# RS485.net
KiCad netlist of a schematic drawn in Altium Designer
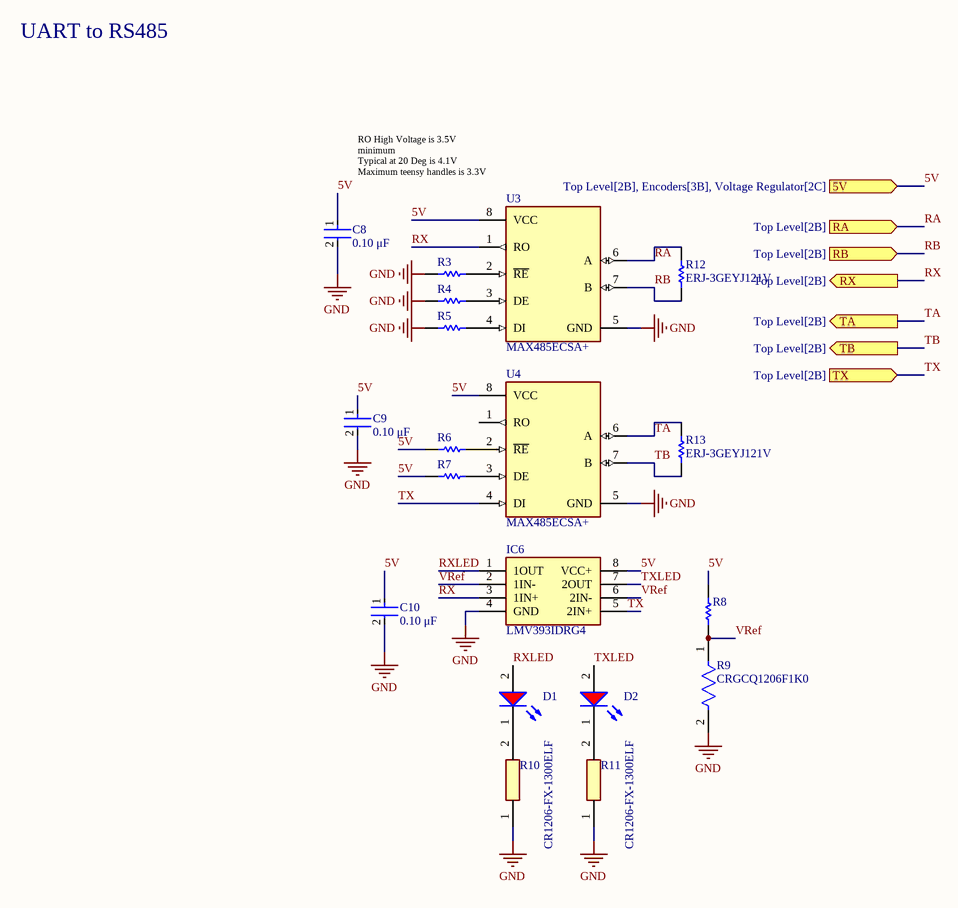
[diagram p0: RS485.SchDoc]

(export (version "E")
  (design (tool "Eeschema 10.0.6"))
  (components
    (comp (ref "C8")
      (value "C1206C104M5RACTU")
      (footprint "FP-C1206C-EB-MFG")
      (description "CAP CER 0.1UF 50V X7R 1206")
      (fields
        (field (name "OCTOPART") "https://octopart.com/c1206c104m5ractu-kemet-129344")
        (field (name "TOLERANCE") "0.2")
        (field (name "CAPACITANCE") "0.10 μF")
      )
      (libsource (lib "Altium Content Vault") (part "b4654b650e69147ec39a6b967a45e02"))
    )
    (comp (ref "C9")
      (value "C1206C104M5RACTU")
      (footprint "FP-C1206C-EB-MFG")
      (description "CAP CER 0.1UF 50V X7R 1206")
      (fields
        (field (name "OCTOPART") "https://octopart.com/c1206c104m5ractu-kemet-129344")
        (field (name "TOLERANCE") "0.2")
        (field (name "CAPACITANCE") "0.10 μF")
      )
      (libsource (lib "Altium Content Vault") (part "b4654b650e69147ec39a6b967a45e02"))
    )
    (comp (ref "C10")
      (value "C1206C104M5RACTU")
      (footprint "FP-C1206C-EB-MFG")
      (description "CAP CER 0.1UF 50V X7R 1206")
      (fields
        (field (name "OCTOPART") "https://octopart.com/c1206c104m5ractu-kemet-129344")
        (field (name "TOLERANCE") "0.2")
        (field (name "CAPACITANCE") "0.10 μF")
      )
      (libsource (lib "Altium Content Vault") (part "b4654b650e69147ec39a6b967a45e02"))
    )
    (comp (ref "D1")
      (value "150120RS75000")
      (footprint "WL-SMCW_1206_150120xx75000")
      (libsource (lib "Altium Content Vault") (part "LED_Red_2A-1K"))
    )
    (comp (ref "D2")
      (value "150120RS75000")
      (footprint "WL-SMCW_1206_150120xx75000")
      (libsource (lib "Altium Content Vault") (part "LED_Red_2A-1K"))
    )
    (comp (ref "IC6")
      (value "LMV393IDRG4")
      (footprint "SamacSys:SOIC127P600X175-8N")
      (description "Integrated Circuit")
      (fields (field (name "MOUSER PART NUMBER") "595-LMV393IDRG4"))
      (libsource (lib "*") (part "LMV393IDRG4"))
    )
    (comp (ref "R3")
      (value "RK73H2BTTD4701F")
      (footprint "RESC3216X70X40NL20T20")
      (fields (field (name "MANUFACTURER") "KOA Speer"))
      (libsource (lib "Altium Content Vault") (part "RES"))
    )
    (comp (ref "R4")
      (value "RK73H2BTTD4701F")
      (footprint "RESC3216X70X40NL20T20")
      (fields (field (name "MANUFACTURER") "KOA Speer"))
      (libsource (lib "Altium Content Vault") (part "RES"))
    )
    (comp (ref "R5")
      (value "RK73H2BTTD4701F")
      (footprint "RESC3216X70X40NL20T20")
      (fields (field (name "MANUFACTURER") "KOA Speer"))
      (libsource (lib "Altium Content Vault") (part "RES"))
    )
    (comp (ref "R6")
      (value "RK73H2BTTD4701F")
      (footprint "RESC3216X70X40NL20T20")
      (fields (field (name "MANUFACTURER") "KOA Speer"))
      (libsource (lib "Altium Content Vault") (part "RES"))
    )
    (comp (ref "R7")
      (value "RK73H2BTTD4701F")
      (footprint "RESC3216X70X40NL20T20")
      (fields (field (name "MANUFACTURER") "KOA Speer"))
      (libsource (lib "Altium Content Vault") (part "RES"))
    )
    (comp (ref "R8")
      (value "RK73B2BTTD222J")
      (footprint "RESC3216X70X40LL20T20")
      (fields (field (name "MANUFACTURER") "KOA Speer"))
      (libsource (lib "Altium Content Vault") (part "RES"))
    )
    (comp (ref "R9")
      (value "CRGCQ1206F1K0")
      (footprint "FP-CRGCQ1206-IPC_C")
      (description "CRGCQ1206 1KΩ 0.25W 1% ±100ppm/°C 200V")
      (fields
        (field (name "MANUFACTURER") "TE Connectivity")
        (field (name "OCTOPART") "https://octopart.com/crgcq1206f1k0-te+connectivity-91018258")
      )
      (libsource (lib "Altium Content Vault") (part "1029c3af85768c4190bb7ad29bc67b5"))
    )
    (comp (ref "R10")
      (value "CR1206-FX-1300ELF")
      (footprint "SamacSys:RESC3216X75N")
      (description "Resistor")
      (fields (field (name "MOUSER PART NUMBER") "652-CR1206FX-1300ELF"))
      (libsource (lib "*") (part "CR1206-FX-1300ELF"))
    )
    (comp (ref "R11")
      (value "CR1206-FX-1300ELF")
      (footprint "SamacSys:RESC3216X75N")
      (description "Resistor")
      (fields (field (name "MOUSER PART NUMBER") "652-CR1206FX-1300ELF"))
      (libsource (lib "*") (part "CR1206-FX-1300ELF"))
    )
    (comp (ref "R12")
      (value "ERJ-3GEYJ121V")
      (footprint "RESC1608X55X30LL15T15")
      (fields (field (name "MANUFACTURER") "Panasonic"))
      (libsource (lib "Altium Content Vault") (part "RES"))
    )
    (comp (ref "R13")
      (value "ERJ-3GEYJ121V")
      (footprint "RESC1608X55X30LL15T15")
      (fields (field (name "MANUFACTURER") "Panasonic"))
      (libsource (lib "Altium Content Vault") (part "RES"))
    )
    (comp (ref "U3")
      (value "MAX485ECSA+")
      (footprint "FP-S8-5-MFG")
      (description "IC TXRX RS485/RS422 8-SOIC")
      (fields
        (field (name "OCTOPART") "https://octopart.com/max485ecsa%2B-maxim+integrated-39397871")
        (field (name "MANUFACTURER") "Maxim Integrated")
      )
      (libsource (lib "Altium Content Vault") (part "a5e355d41674bc2bebc6d79e25ee122"))
    )
    (comp (ref "U4")
      (value "MAX485ECSA+")
      (footprint "FP-S8-5-MFG")
      (description "IC TXRX RS485/RS422 8-SOIC")
      (fields
        (field (name "OCTOPART") "https://octopart.com/max485ecsa%2B-maxim+integrated-39397871")
        (field (name "MANUFACTURER") "Maxim Integrated")
      )
      (libsource (lib "Altium Content Vault") (part "a5e355d41674bc2bebc6d79e25ee122"))
    )
  )
  (nets
    (net (code "1") (name "/5V") (class "Default")
      (node (ref "C10") (pin "1") (pinfunction "1_1") (pintype "passive"))
      (node (ref "C8") (pin "1") (pinfunction "1_1") (pintype "passive"))
      (node (ref "C9") (pin "1") (pinfunction "1_1") (pintype "passive"))
      (node (ref "IC6") (pin "8") (pinfunction "VCC+_8") (pintype "passive"))
      (node (ref "R6") (pin "2") (pinfunction "2_2") (pintype "passive"))
      (node (ref "R7") (pin "2") (pinfunction "2_2") (pintype "passive"))
      (node (ref "R8") (pin "2") (pinfunction "2_2") (pintype "passive"))
      (node (ref "U3") (pin "8") (pinfunction "VCC_8") (pintype "power_in"))
      (node (ref "U4") (pin "8") (pinfunction "VCC_8") (pintype "power_in"))
    )
    (net (code "2") (name "/RA") (class "Default")
      (node (ref "R12") (pin "2") (pinfunction "2_2") (pintype "passive"))
      (node (ref "U3") (pin "6") (pinfunction "A_6") (pintype "bidirectional"))
    )
    (net (code "3") (name "/RB") (class "Default")
      (node (ref "R12") (pin "1") (pinfunction "1_1") (pintype "passive"))
      (node (ref "U3") (pin "7") (pinfunction "B_7") (pintype "bidirectional"))
    )
    (net (code "4") (name "/RX") (class "Default")
      (node (ref "IC6") (pin "3") (pinfunction "1IN+_3") (pintype "passive"))
      (node (ref "U3") (pin "1") (pinfunction "RO_1") (pintype "output"))
    )
    (net (code "5") (name "/RXLED") (class "Default")
      (node (ref "D1") (pin "2") (pinfunction "A_2") (pintype "passive"))
      (node (ref "IC6") (pin "1") (pinfunction "1OUT_1") (pintype "passive"))
    )
    (net (code "6") (name "/TA") (class "Default")
      (node (ref "R13") (pin "2") (pinfunction "2_2") (pintype "passive"))
      (node (ref "U4") (pin "6") (pinfunction "A_6") (pintype "bidirectional"))
    )
    (net (code "7") (name "/TB") (class "Default")
      (node (ref "R13") (pin "1") (pinfunction "1_1") (pintype "passive"))
      (node (ref "U4") (pin "7") (pinfunction "B_7") (pintype "bidirectional"))
    )
    (net (code "8") (name "/TX") (class "Default")
      (node (ref "IC6") (pin "5") (pinfunction "2IN+_5") (pintype "passive"))
      (node (ref "U4") (pin "4") (pinfunction "DI_4") (pintype "input"))
    )
    (net (code "9") (name "/TXLED") (class "Default")
      (node (ref "D2") (pin "2") (pinfunction "A_2") (pintype "passive"))
      (node (ref "IC6") (pin "7") (pinfunction "2OUT_7") (pintype "passive"))
    )
    (net (code "10") (name "/VRef") (class "Default")
      (node (ref "IC6") (pin "2") (pinfunction "1IN-_2") (pintype "passive"))
      (node (ref "IC6") (pin "6") (pinfunction "2IN-_6") (pintype "passive"))
      (node (ref "R8") (pin "1") (pinfunction "1_1") (pintype "passive"))
      (node (ref "R9") (pin "1") (pinfunction "1_1") (pintype "passive"))
    )
    (net (code "11") (name "GND") (class "Default")
      (node (ref "C10") (pin "2") (pinfunction "2_2") (pintype "passive"))
      (node (ref "C8") (pin "2") (pinfunction "2_2") (pintype "passive"))
      (node (ref "C9") (pin "2") (pinfunction "2_2") (pintype "passive"))
      (node (ref "IC6") (pin "4") (pinfunction "GND_4") (pintype "passive"))
      (node (ref "R10") (pin "1") (pinfunction "1_1") (pintype "passive"))
      (node (ref "R11") (pin "1") (pinfunction "1_1") (pintype "passive"))
      (node (ref "R3") (pin "2") (pinfunction "2_2") (pintype "passive"))
      (node (ref "R4") (pin "2") (pinfunction "2_2") (pintype "passive"))
      (node (ref "R5") (pin "2") (pinfunction "2_2") (pintype "passive"))
      (node (ref "R9") (pin "2") (pinfunction "2_2") (pintype "passive"))
      (node (ref "U3") (pin "5") (pinfunction "GND_5") (pintype "power_in"))
      (node (ref "U4") (pin "5") (pinfunction "GND_5") (pintype "power_in"))
    )
    (net (code "12") (name "Net-(D1-K)") (class "Default")
      (node (ref "D1") (pin "1") (pinfunction "K_1") (pintype "passive"))
      (node (ref "R10") (pin "2") (pinfunction "2_2") (pintype "passive"))
    )
    (net (code "13") (name "Net-(D2-K)") (class "Default")
      (node (ref "D2") (pin "1") (pinfunction "K_1") (pintype "passive"))
      (node (ref "R11") (pin "2") (pinfunction "2_2") (pintype "passive"))
    )
    (net (code "14") (name "Net-(U3-DE)") (class "Default")
      (node (ref "R4") (pin "1") (pinfunction "1_1") (pintype "passive"))
      (node (ref "U3") (pin "3") (pinfunction "DE_3") (pintype "input"))
    )
    (net (code "15") (name "Net-(U3-DI)") (class "Default")
      (node (ref "R5") (pin "1") (pinfunction "1_1") (pintype "passive"))
      (node (ref "U3") (pin "4") (pinfunction "DI_4") (pintype "input"))
    )
    (net (code "16") (name "Net-(U3-~{RE})") (class "Default")
      (node (ref "R3") (pin "1") (pinfunction "1_1") (pintype "passive"))
      (node (ref "U3") (pin "2") (pinfunction "~{RE}_2") (pintype "input"))
    )
    (net (code "17") (name "Net-(U4-DE)") (class "Default")
      (node (ref "R7") (pin "1") (pinfunction "1_1") (pintype "passive"))
      (node (ref "U4") (pin "3") (pinfunction "DE_3") (pintype "input"))
    )
    (net (code "18") (name "Net-(U4-~{RE})") (class "Default")
      (node (ref "R6") (pin "1") (pinfunction "1_1") (pintype "passive"))
      (node (ref "U4") (pin "2") (pinfunction "~{RE}_2") (pintype "input"))
    )
    (net (code "19") (name "unconnected-(U4-RO-Pad1)") (class "Default")
      (node (ref "U4") (pin "1") (pinfunction "RO_1") (pintype "output"))
    )
  )
)
